# Gripper_Control_Board.net
KiCad netlist of a schematic drawn in EAGLE
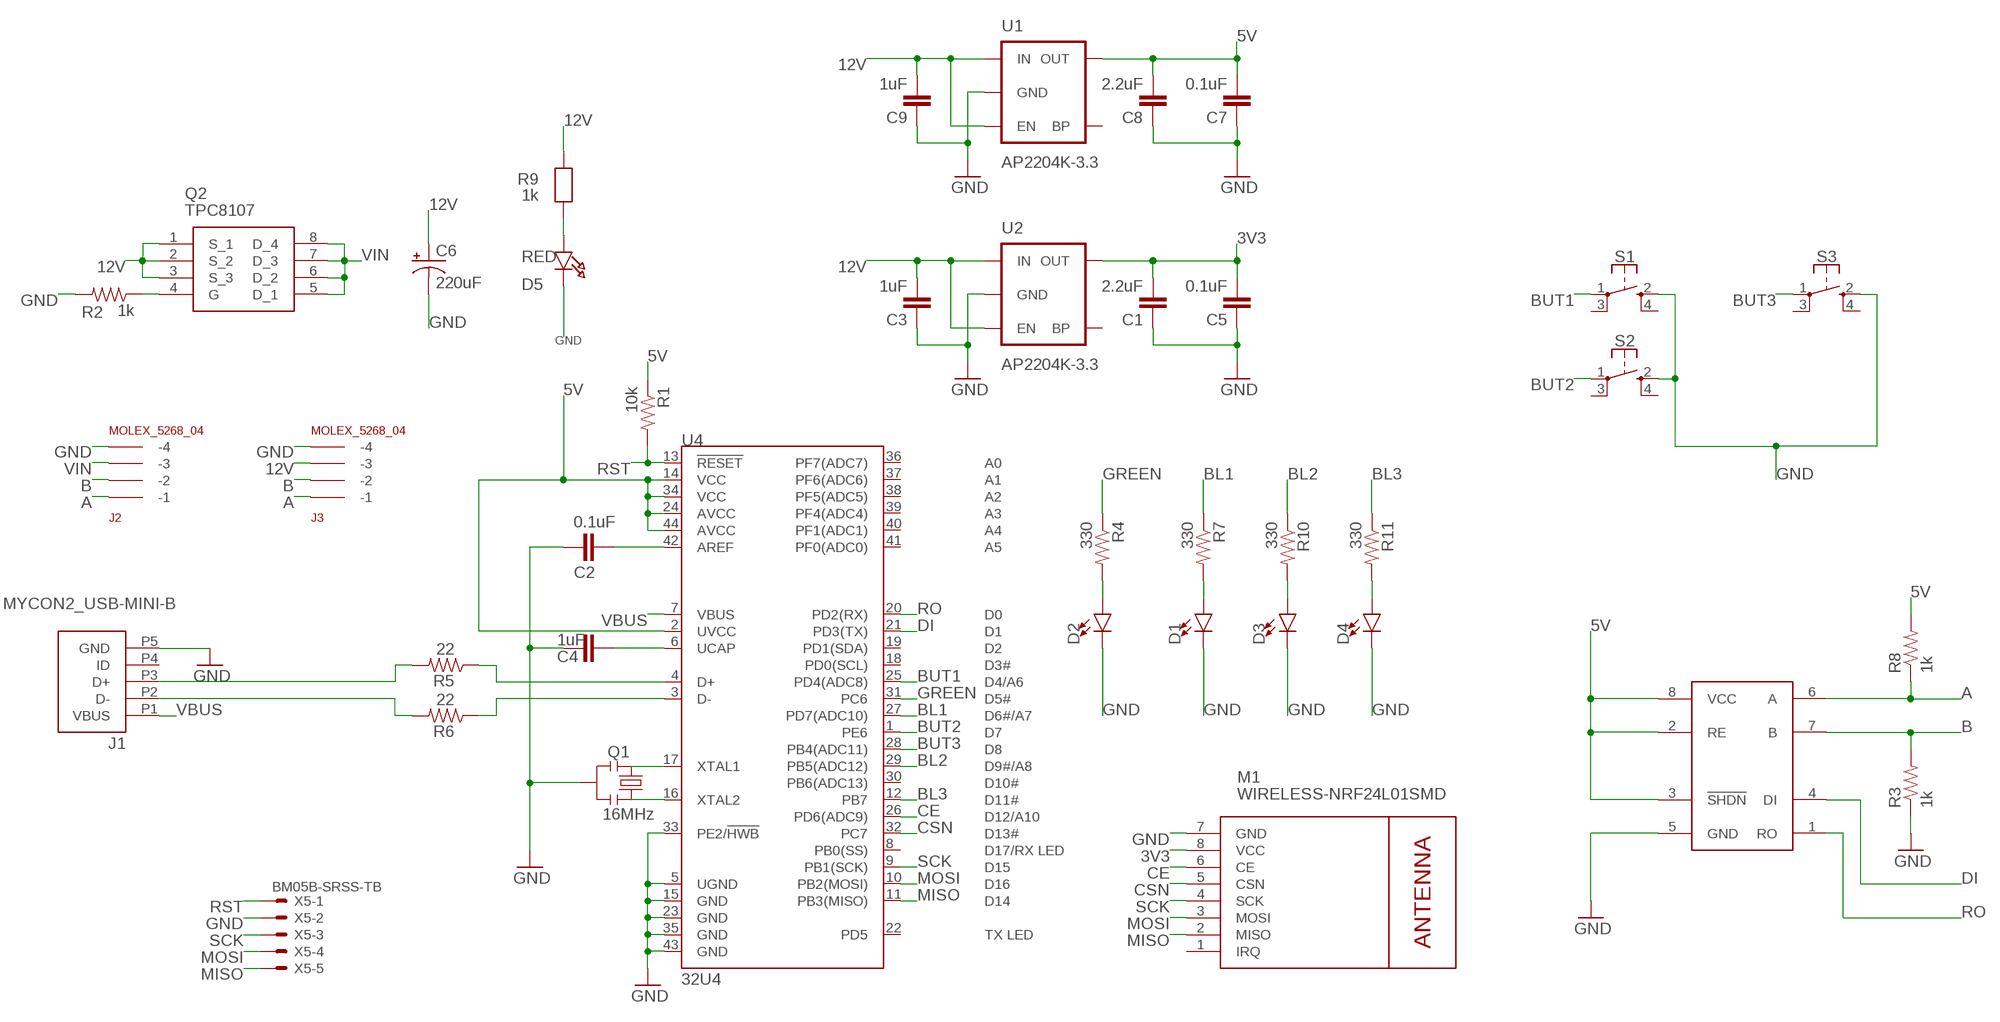
[diagram p0: schematic, sheet 1]

(export (version "E")
  (design (tool "Eeschema 10.0.6"))
  (components
    (comp (ref "C1")
      (value "2.2uF")
      (footprint "eagle-import:0603-CAP")
      (libsource (lib "eagle-import") (part "CAP0603-CAP"))
    )
    (comp (ref "C2")
      (value "0.1uF")
      (footprint "eagle-import:0603-CAP")
      (libsource (lib "eagle-import") (part "CAP0603-CAP"))
    )
    (comp (ref "C3")
      (value "1uF")
      (footprint "eagle-import:0603-CAP")
      (libsource (lib "eagle-import") (part "CAP0603-CAP"))
    )
    (comp (ref "C4")
      (value "1uF")
      (footprint "eagle-import:0603-CAP")
      (libsource (lib "eagle-import") (part "CAP0603-CAP"))
    )
    (comp (ref "C5")
      (value "0.1uF")
      (footprint "eagle-import:0603-CAP")
      (libsource (lib "eagle-import") (part "CAP0603-CAP"))
    )
    (comp (ref "C6")
      (value "220uF")
      (footprint "eagle-import:PANASONIC_D")
      (libsource (lib "eagle-import") (part "100UF-POLAR-25V-20%(ELEC)"))
    )
    (comp (ref "C7")
      (value "0.1uF")
      (footprint "eagle-import:0603-CAP")
      (libsource (lib "eagle-import") (part "CAP0603-CAP"))
    )
    (comp (ref "C8")
      (value "2.2uF")
      (footprint "eagle-import:0603-CAP")
      (libsource (lib "eagle-import") (part "CAP0603-CAP"))
    )
    (comp (ref "C9")
      (value "1uF")
      (footprint "eagle-import:0603-CAP")
      (libsource (lib "eagle-import") (part "CAP0603-CAP"))
    )
    (comp (ref "D1")
      (value "LED0603")
      (footprint "eagle-import:LED-0603")
      (libsource (lib "eagle-import") (part "LED0603"))
    )
    (comp (ref "D2")
      (value "LED0603")
      (footprint "eagle-import:LED-0603")
      (libsource (lib "eagle-import") (part "LED0603"))
    )
    (comp (ref "D3")
      (value "LED0603")
      (footprint "eagle-import:LED-0603")
      (libsource (lib "eagle-import") (part "LED0603"))
    )
    (comp (ref "D4")
      (value "LED0603")
      (footprint "eagle-import:LED-0603")
      (libsource (lib "eagle-import") (part "LED0603"))
    )
    (comp (ref "D5")
      (value "RED")
      (footprint "eagle-import:CHIPLED_0603")
      (libsource (lib "eagle-import") (part "microbuilder_LED0603"))
    )
    (comp (ref "J1")
      (value "MYCON2_USB-MINI-B")
      (footprint "eagle-import:CON2_USB_MICRO_B_AT")
      (libsource (lib "eagle-import") (part "MYCON2_USB-MINI-B"))
    )
    (comp (ref "J2")
      (value "MOLEX_5268_04")
      (footprint "eagle-import:5267-4")
      (libsource (lib "eagle-import") (part "MOLEX_5268_04"))
    )
    (comp (ref "J3")
      (value "MOLEX_5268_04")
      (footprint "eagle-import:5267-4")
      (libsource (lib "eagle-import") (part "MOLEX_5268_04"))
    )
    (comp (ref "M1")
      (value "WIRELESS-NRF24L01SMD")
      (footprint "eagle-import:WIRELESS-NRF24L01-SMD")
      (libsource (lib "eagle-import") (part "WIRELESS-NRF24L01SMD"))
    )
    (comp (ref "Q1")
      (value "16MHz")
      (footprint "eagle-import:RESONATOR-SMD")
      (libsource (lib "eagle-import") (part "RESONATORSMD"))
    )
    (comp (ref "Q2")
      (value "TPC8107")
      (footprint "eagle-import:SOIC127P600X175-8N")
      (fields
        (field (name "MANUFACTURER_PART_NUMBER") "DMG4413LSS-13")
        (field (name "MOUSER_PART_NUMBER") "621-DMG4413LSS-13")
        (field (name "RS_PART_NUMBER") "7514102P")
      )
      (libsource (lib "eagle-import") (part "TPC8107"))
    )
    (comp (ref "R1")
      (value "10k")
      (footprint "eagle-import:0603-RES")
      (libsource (lib "eagle-import") (part "RESISTOR0603"))
    )
    (comp (ref "R2")
      (value "1k")
      (footprint "eagle-import:0603")
      (libsource (lib "eagle-import") (part "1KOHM-0603-1/10W-1%"))
    )
    (comp (ref "R3")
      (value "1k")
      (footprint "eagle-import:0603-RES")
      (libsource (lib "eagle-import") (part "RESISTOR0603-RES"))
    )
    (comp (ref "R4")
      (value "330")
      (footprint "eagle-import:0603-RES")
      (libsource (lib "eagle-import") (part "RESISTOR0603"))
    )
    (comp (ref "R5")
      (value "22")
      (footprint "eagle-import:0603-RES")
      (fields (field (name "SPICEPREFIX") "R"))
      (libsource (lib "eagle-import") (part "RESISTOR0603"))
    )
    (comp (ref "R6")
      (value "22")
      (footprint "eagle-import:0603-RES")
      (libsource (lib "eagle-import") (part "RESISTOR0603"))
    )
    (comp (ref "R7")
      (value "330")
      (footprint "eagle-import:0603-RES")
      (fields (field (name "SPICEPREFIX") "R"))
      (libsource (lib "eagle-import") (part "RESISTOR0603"))
    )
    (comp (ref "R8")
      (value "1k")
      (footprint "eagle-import:0603-RES")
      (libsource (lib "eagle-import") (part "RESISTOR0603-RES"))
    )
    (comp (ref "R9")
      (value "1k")
      (footprint "eagle-import:0603-MINI")
      (libsource (lib "eagle-import") (part "RESISTOR0603MINI"))
    )
    (comp (ref "R10")
      (value "330")
      (footprint "eagle-import:0603-RES")
      (libsource (lib "eagle-import") (part "RESISTOR0603"))
    )
    (comp (ref "R11")
      (value "330")
      (footprint "eagle-import:0603-RES")
      (libsource (lib "eagle-import") (part "RESISTOR0603"))
    )
    (comp (ref "S1")
      (value "SKSGAAE010")
      (footprint "eagle-import:SKSG")
      (fields (field (name "MOUSER_PART_NUMBER") "688-SKSGAAE010"))
      (libsource (lib "eagle-import") (part "SKSGAAE010"))
    )
    (comp (ref "S2")
      (value "SKSGAAE010")
      (footprint "eagle-import:SKSG")
      (fields (field (name "MOUSER_PART_NUMBER") "688-SKSGAAE010"))
      (libsource (lib "eagle-import") (part "SKSGAAE010"))
    )
    (comp (ref "S3")
      (value "SKSGAAE010")
      (footprint "eagle-import:SKSG")
      (fields (field (name "MOUSER_PART_NUMBER") "688-SKSGAAE010"))
      (libsource (lib "eagle-import") (part "SKSGAAE010"))
    )
    (comp (ref "U1")
      (value "AP2204K-3.3")
      (footprint "eagle-import:SOT23-5")
      (libsource (lib "eagle-import") (part "V_REG_LDOSMD"))
    )
    (comp (ref "U2")
      (value "AP2204K-3.3")
      (footprint "eagle-import:SOT23-5")
      (libsource (lib "eagle-import") (part "V_REG_LDOSMD"))
    )
    (comp (ref "U3")
      (value "MAX13487")
      (footprint "eagle-import:MAX13487")
      (libsource (lib "eagle-import") (part "MAX13487SOIC"))
    )
    (comp (ref "U4")
      (value "32U4")
      (footprint "eagle-import:QFN-44-NOPAD")
      (libsource (lib "eagle-import") (part "ATMEGA32U4QFN2"))
    )
    (comp (ref "X5")
      (value "BM05B-SRSS-TB")
      (footprint "eagle-import:BM05B-SRSS-TB")
      (libsource (lib "eagle-import") (part "?M05B-SRSS-TBB"))
    )
  )
  (nets
    (net (code "1") (name "/3V3") (class "Default")
      (node (ref "C1") (pin "2") (pinfunction "2_2") (pintype "passive"))
      (node (ref "C5") (pin "2") (pinfunction "2_2") (pintype "passive"))
      (node (ref "M1") (pin "8") (pinfunction "VCC_8") (pintype "power_in"))
      (node (ref "U2") (pin "5") (pinfunction "OUT_5") (pintype "passive"))
    )
    (net (code "2") (name "/5V") (class "Default")
      (node (ref "C7") (pin "2") (pinfunction "2_2") (pintype "passive"))
      (node (ref "C8") (pin "2") (pinfunction "2_2") (pintype "passive"))
      (node (ref "R1") (pin "1") (pinfunction "1_1") (pintype "passive"))
      (node (ref "R8") (pin "2") (pinfunction "2_2") (pintype "passive"))
      (node (ref "U1") (pin "5") (pinfunction "OUT_5") (pintype "passive"))
      (node (ref "U3") (pin "2") (pinfunction "RE_2") (pintype "bidirectional"))
      (node (ref "U3") (pin "3") (pinfunction "~{SHDN}_3") (pintype "bidirectional"))
      (node (ref "U3") (pin "8") (pinfunction "VCC_8") (pintype "power_in"))
      (node (ref "U4") (pin "14") (pinfunction "VCC_14") (pintype "bidirectional"))
      (node (ref "U4") (pin "2") (pinfunction "UVCC_2") (pintype "bidirectional"))
      (node (ref "U4") (pin "24") (pinfunction "AVCC_24") (pintype "bidirectional"))
      (node (ref "U4") (pin "34") (pinfunction "VCC_34") (pintype "bidirectional"))
      (node (ref "U4") (pin "44") (pinfunction "AVCC_44") (pintype "bidirectional"))
    )
    (net (code "3") (name "/12V") (class "Default")
      (node (ref "C3") (pin "2") (pinfunction "2_2") (pintype "passive"))
      (node (ref "C6") (pin "+") (pinfunction "+_+") (pintype "passive"))
      (node (ref "C9") (pin "2") (pinfunction "2_2") (pintype "passive"))
      (node (ref "J3") (pin "P$3") (pinfunction "-3_P$3") (pintype "bidirectional"))
      (node (ref "Q2") (pin "1") (pinfunction "S_1_1") (pintype "bidirectional"))
      (node (ref "Q2") (pin "2") (pinfunction "S_2_2") (pintype "bidirectional"))
      (node (ref "Q2") (pin "3") (pinfunction "S_3_3") (pintype "bidirectional"))
      (node (ref "R9") (pin "2") (pinfunction "2_2") (pintype "passive"))
      (node (ref "U1") (pin "1") (pinfunction "IN_1") (pintype "input"))
      (node (ref "U1") (pin "3") (pinfunction "EN_3") (pintype "input"))
      (node (ref "U2") (pin "1") (pinfunction "IN_1") (pintype "input"))
      (node (ref "U2") (pin "3") (pinfunction "EN_3") (pintype "input"))
    )
    (net (code "4") (name "/A") (class "Default")
      (node (ref "J2") (pin "P$1") (pinfunction "-1_P$1") (pintype "bidirectional"))
      (node (ref "J3") (pin "P$1") (pinfunction "-1_P$1") (pintype "bidirectional"))
      (node (ref "R8") (pin "1") (pinfunction "1_1") (pintype "passive"))
      (node (ref "U3") (pin "6") (pinfunction "A_6") (pintype "bidirectional"))
    )
    (net (code "5") (name "/B") (class "Default")
      (node (ref "J2") (pin "P$2") (pinfunction "-2_P$2") (pintype "bidirectional"))
      (node (ref "J3") (pin "P$2") (pinfunction "-2_P$2") (pintype "bidirectional"))
      (node (ref "R3") (pin "2") (pinfunction "2_2") (pintype "passive"))
      (node (ref "U3") (pin "7") (pinfunction "B_7") (pintype "bidirectional"))
    )
    (net (code "6") (name "/BL1") (class "Default")
      (node (ref "R7") (pin "1") (pinfunction "1_1") (pintype "passive"))
      (node (ref "U4") (pin "27") (pinfunction "PD7(ADC10)_27") (pintype "bidirectional"))
    )
    (net (code "7") (name "/BL2") (class "Default")
      (node (ref "R10") (pin "1") (pinfunction "1_1") (pintype "passive"))
      (node (ref "U4") (pin "29") (pinfunction "PB5(ADC12)_29") (pintype "bidirectional"))
    )
    (net (code "8") (name "/BL3") (class "Default")
      (node (ref "R11") (pin "1") (pinfunction "1_1") (pintype "passive"))
      (node (ref "U4") (pin "12") (pinfunction "PB7_12") (pintype "bidirectional"))
    )
    (net (code "9") (name "/BUT1") (class "Default")
      (node (ref "S1") (pin "1") (pinfunction "1_1") (pintype "passive"))
      (node (ref "U4") (pin "25") (pinfunction "PD4(ADC8)_25") (pintype "bidirectional"))
    )
    (net (code "10") (name "/BUT2") (class "Default")
      (node (ref "S2") (pin "1") (pinfunction "1_1") (pintype "passive"))
      (node (ref "U4") (pin "1") (pinfunction "PE6_1") (pintype "bidirectional"))
    )
    (net (code "11") (name "/BUT3") (class "Default")
      (node (ref "S3") (pin "1") (pinfunction "1_1") (pintype "passive"))
      (node (ref "U4") (pin "28") (pinfunction "PB4(ADC11)_28") (pintype "bidirectional"))
    )
    (net (code "12") (name "/CE") (class "Default")
      (node (ref "M1") (pin "6") (pinfunction "CE_6") (pintype "bidirectional"))
      (node (ref "U4") (pin "26") (pinfunction "PD6(ADC9)_26") (pintype "bidirectional"))
    )
    (net (code "13") (name "/CSN") (class "Default")
      (node (ref "M1") (pin "5") (pinfunction "CSN_5") (pintype "bidirectional"))
      (node (ref "U4") (pin "32") (pinfunction "PC7_32") (pintype "bidirectional"))
    )
    (net (code "14") (name "/DI") (class "Default")
      (node (ref "U3") (pin "4") (pinfunction "DI_4") (pintype "input"))
      (node (ref "U4") (pin "21") (pinfunction "PD3(TX)_21") (pintype "bidirectional"))
    )
    (net (code "15") (name "/GREEN") (class "Default")
      (node (ref "R4") (pin "1") (pinfunction "1_1") (pintype "passive"))
      (node (ref "U4") (pin "31") (pinfunction "PC6_31") (pintype "bidirectional"))
    )
    (net (code "16") (name "/MISO") (class "Default")
      (node (ref "M1") (pin "2") (pinfunction "MISO_2") (pintype "bidirectional"))
      (node (ref "U4") (pin "11") (pinfunction "PB3(MISO)_11") (pintype "bidirectional"))
      (node (ref "X5") (pin "5") (pinfunction "S_5") (pintype "passive"))
    )
    (net (code "17") (name "/MOSI") (class "Default")
      (node (ref "M1") (pin "3") (pinfunction "MOSI_3") (pintype "bidirectional"))
      (node (ref "U4") (pin "10") (pinfunction "PB2(MOSI)_10") (pintype "bidirectional"))
      (node (ref "X5") (pin "4") (pinfunction "S_4") (pintype "passive"))
    )
    (net (code "18") (name "/RO") (class "Default")
      (node (ref "U3") (pin "1") (pinfunction "RO_1") (pintype "output"))
      (node (ref "U4") (pin "20") (pinfunction "PD2(RX)_20") (pintype "bidirectional"))
    )
    (net (code "19") (name "/RST") (class "Default")
      (node (ref "R1") (pin "2") (pinfunction "2_2") (pintype "passive"))
      (node (ref "U4") (pin "13") (pinfunction "~{RESET}_13") (pintype "bidirectional"))
      (node (ref "X5") (pin "1") (pinfunction "S_1") (pintype "passive"))
    )
    (net (code "20") (name "/SCK") (class "Default")
      (node (ref "M1") (pin "4") (pinfunction "SCK_4") (pintype "bidirectional"))
      (node (ref "U4") (pin "9") (pinfunction "PB1(SCK)_9") (pintype "bidirectional"))
      (node (ref "X5") (pin "3") (pinfunction "S_3") (pintype "passive"))
    )
    (net (code "21") (name "/VBUS") (class "Default")
      (node (ref "J1") (pin "P1") (pinfunction "VBUS_P1") (pintype "power_in"))
      (node (ref "U4") (pin "7") (pinfunction "VBUS_7") (pintype "bidirectional"))
    )
    (net (code "22") (name "/VIN") (class "Default")
      (node (ref "J2") (pin "P$3") (pinfunction "-3_P$3") (pintype "bidirectional"))
      (node (ref "Q2") (pin "5") (pinfunction "D_1_5") (pintype "bidirectional"))
      (node (ref "Q2") (pin "6") (pinfunction "D_2_6") (pintype "bidirectional"))
      (node (ref "Q2") (pin "7") (pinfunction "D_3_7") (pintype "bidirectional"))
      (node (ref "Q2") (pin "8") (pinfunction "D_4_8") (pintype "bidirectional"))
    )
    (net (code "23") (name "GND") (class "Default")
      (node (ref "C1") (pin "1") (pinfunction "1_1") (pintype "passive"))
      (node (ref "C2") (pin "1") (pinfunction "1_1") (pintype "passive"))
      (node (ref "C3") (pin "1") (pinfunction "1_1") (pintype "passive"))
      (node (ref "C4") (pin "1") (pinfunction "1_1") (pintype "passive"))
      (node (ref "C5") (pin "1") (pinfunction "1_1") (pintype "passive"))
      (node (ref "C6") (pin "-") (pinfunction "-_-") (pintype "passive"))
      (node (ref "C7") (pin "1") (pinfunction "1_1") (pintype "passive"))
      (node (ref "C8") (pin "1") (pinfunction "1_1") (pintype "passive"))
      (node (ref "C9") (pin "1") (pinfunction "1_1") (pintype "passive"))
      (node (ref "D1") (pin "C") (pinfunction "C_C") (pintype "passive"))
      (node (ref "D2") (pin "C") (pinfunction "C_C") (pintype "passive"))
      (node (ref "D3") (pin "C") (pinfunction "C_C") (pintype "passive"))
      (node (ref "D4") (pin "C") (pinfunction "C_C") (pintype "passive"))
      (node (ref "D5") (pin "C") (pinfunction "C_C") (pintype "passive"))
      (node (ref "J1") (pin "P5") (pinfunction "GND_P5") (pintype "passive"))
      (node (ref "J2") (pin "P$4") (pinfunction "-4_P$4") (pintype "bidirectional"))
      (node (ref "J3") (pin "P$4") (pinfunction "-4_P$4") (pintype "bidirectional"))
      (node (ref "M1") (pin "7") (pinfunction "GND_7") (pintype "power_in"))
      (node (ref "Q1") (pin "2") (pinfunction "2_2") (pintype "passive"))
      (node (ref "R2") (pin "2") (pinfunction "2_2") (pintype "passive"))
      (node (ref "R3") (pin "1") (pinfunction "1_1") (pintype "passive"))
      (node (ref "S1") (pin "2") (pinfunction "3_2") (pintype "passive"))
      (node (ref "S2") (pin "2") (pinfunction "3_2") (pintype "passive"))
      (node (ref "S3") (pin "2") (pinfunction "3_2") (pintype "passive"))
      (node (ref "U1") (pin "2") (pinfunction "GND_2") (pintype "input"))
      (node (ref "U2") (pin "2") (pinfunction "GND_2") (pintype "input"))
      (node (ref "U3") (pin "5") (pinfunction "GND_5") (pintype "power_in"))
      (node (ref "U4") (pin "15") (pinfunction "GND_15") (pintype "bidirectional"))
      (node (ref "U4") (pin "23") (pinfunction "GND_23") (pintype "bidirectional"))
      (node (ref "U4") (pin "33") (pinfunction "PE2/~{HWB}_33") (pintype "bidirectional"))
      (node (ref "U4") (pin "35") (pinfunction "GND_35") (pintype "bidirectional"))
      (node (ref "U4") (pin "43") (pinfunction "GND_43") (pintype "bidirectional"))
      (node (ref "U4") (pin "5") (pinfunction "UGND_5") (pintype "bidirectional"))
      (node (ref "X5") (pin "2") (pinfunction "S_2") (pintype "passive"))
    )
    (net (code "24") (name "Net-(D1-PadA)") (class "Default")
      (node (ref "D1") (pin "A") (pinfunction "A_A") (pintype "passive"))
      (node (ref "R7") (pin "2") (pinfunction "2_2") (pintype "passive"))
    )
    (net (code "25") (name "Net-(D2-PadA)") (class "Default")
      (node (ref "D2") (pin "A") (pinfunction "A_A") (pintype "passive"))
      (node (ref "R4") (pin "2") (pinfunction "2_2") (pintype "passive"))
    )
    (net (code "26") (name "Net-(D3-PadA)") (class "Default")
      (node (ref "D3") (pin "A") (pinfunction "A_A") (pintype "passive"))
      (node (ref "R10") (pin "2") (pinfunction "2_2") (pintype "passive"))
    )
    (net (code "27") (name "Net-(D4-PadA)") (class "Default")
      (node (ref "D4") (pin "A") (pinfunction "A_A") (pintype "passive"))
      (node (ref "R11") (pin "2") (pinfunction "2_2") (pintype "passive"))
    )
    (net (code "28") (name "Net-(D5-PadA)") (class "Default")
      (node (ref "D5") (pin "A") (pinfunction "A_A") (pintype "passive"))
      (node (ref "R9") (pin "1") (pinfunction "1_1") (pintype "passive"))
    )
    (net (code "29") (name "Net-(J1-D+)") (class "Default")
      (node (ref "J1") (pin "P3") (pinfunction "D+_P3") (pintype "bidirectional"))
      (node (ref "R5") (pin "2") (pinfunction "2_2") (pintype "passive"))
    )
    (net (code "30") (name "Net-(J1-D-)") (class "Default")
      (node (ref "J1") (pin "P2") (pinfunction "D-_P2") (pintype "bidirectional"))
      (node (ref "R6") (pin "2") (pinfunction "2_2") (pintype "passive"))
    )
    (net (code "31") (name "Net-(Q2-G)") (class "Default")
      (node (ref "Q2") (pin "4") (pinfunction "G_4") (pintype "bidirectional"))
      (node (ref "R2") (pin "1") (pinfunction "1_1") (pintype "passive"))
    )
    (net (code "32") (name "Net-(U4-AREF)") (class "Default")
      (node (ref "C2") (pin "2") (pinfunction "2_2") (pintype "passive"))
      (node (ref "U4") (pin "42") (pinfunction "AREF_42") (pintype "bidirectional"))
    )
    (net (code "33") (name "Net-(U4-D+)") (class "Default")
      (node (ref "R5") (pin "1") (pinfunction "1_1") (pintype "passive"))
      (node (ref "U4") (pin "4") (pinfunction "D+_4") (pintype "bidirectional"))
    )
    (net (code "34") (name "Net-(U4-D-)") (class "Default")
      (node (ref "R6") (pin "1") (pinfunction "1_1") (pintype "passive"))
      (node (ref "U4") (pin "3") (pinfunction "D-_3") (pintype "bidirectional"))
    )
    (net (code "35") (name "Net-(U4-UCAP)") (class "Default")
      (node (ref "C4") (pin "2") (pinfunction "2_2") (pintype "passive"))
      (node (ref "U4") (pin "6") (pinfunction "UCAP_6") (pintype "bidirectional"))
    )
    (net (code "36") (name "Net-(U4-XTAL1)") (class "Default")
      (node (ref "Q1") (pin "1") (pinfunction "1_1") (pintype "passive"))
      (node (ref "U4") (pin "17") (pinfunction "XTAL1_17") (pintype "bidirectional"))
    )
    (net (code "37") (name "Net-(U4-XTAL2)") (class "Default")
      (node (ref "Q1") (pin "3") (pinfunction "3_3") (pintype "passive"))
      (node (ref "U4") (pin "16") (pinfunction "XTAL2_16") (pintype "bidirectional"))
    )
    (net (code "38") (name "unconnected-(J1-ID-PadP4)") (class "Default")
      (node (ref "J1") (pin "P4") (pinfunction "ID_P4") (pintype "bidirectional"))
    )
    (net (code "39") (name "unconnected-(M1-IRQ-Pad1)") (class "Default")
      (node (ref "M1") (pin "1") (pinfunction "IRQ_1") (pintype "bidirectional"))
    )
    (net (code "40") (name "unconnected-(S1-2-Pad3)") (class "Default")
      (node (ref "S1") (pin "3") (pinfunction "2_3") (pintype "passive"))
    )
    (net (code "41") (name "unconnected-(S1-Pad4)") (class "Default")
      (node (ref "S1") (pin "4") (pinfunction "4_4") (pintype "passive"))
    )
    (net (code "42") (name "unconnected-(S2-2-Pad3)") (class "Default")
      (node (ref "S2") (pin "3") (pinfunction "2_3") (pintype "passive"))
    )
    (net (code "43") (name "unconnected-(S2-Pad4)") (class "Default")
      (node (ref "S2") (pin "4") (pinfunction "4_4") (pintype "passive"))
    )
    (net (code "44") (name "unconnected-(S3-2-Pad3)") (class "Default")
      (node (ref "S3") (pin "3") (pinfunction "2_3") (pintype "passive"))
    )
    (net (code "45") (name "unconnected-(S3-Pad4)") (class "Default")
      (node (ref "S3") (pin "4") (pinfunction "4_4") (pintype "passive"))
    )
    (net (code "46") (name "unconnected-(U1-BP-Pad4)") (class "Default")
      (node (ref "U1") (pin "4") (pinfunction "BP_4") (pintype "input"))
    )
    (net (code "47") (name "unconnected-(U2-BP-Pad4)") (class "Default")
      (node (ref "U2") (pin "4") (pinfunction "BP_4") (pintype "input"))
    )
    (net (code "48") (name "unconnected-(U4-PB0(SS)-Pad8)") (class "Default")
      (node (ref "U4") (pin "8") (pinfunction "PB0(SS)_8") (pintype "bidirectional"))
    )
    (net (code "49") (name "unconnected-(U4-PB6(ADC13)-Pad30)") (class "Default")
      (node (ref "U4") (pin "30") (pinfunction "PB6(ADC13)_30") (pintype "bidirectional"))
    )
    (net (code "50") (name "unconnected-(U4-PD0(SCL)-Pad18)") (class "Default")
      (node (ref "U4") (pin "18") (pinfunction "PD0(SCL)_18") (pintype "bidirectional"))
    )
    (net (code "51") (name "unconnected-(U4-PD1(SDA)-Pad19)") (class "Default")
      (node (ref "U4") (pin "19") (pinfunction "PD1(SDA)_19") (pintype "bidirectional"))
    )
    (net (code "52") (name "unconnected-(U4-PD5-Pad22)") (class "Default")
      (node (ref "U4") (pin "22") (pinfunction "PD5_22") (pintype "bidirectional"))
    )
    (net (code "53") (name "unconnected-(U4-PF0(ADC0)-Pad41)") (class "Default")
      (node (ref "U4") (pin "41") (pinfunction "PF0(ADC0)_41") (pintype "bidirectional"))
    )
    (net (code "54") (name "unconnected-(U4-PF1(ADC1)-Pad40)") (class "Default")
      (node (ref "U4") (pin "40") (pinfunction "PF1(ADC1)_40") (pintype "bidirectional"))
    )
    (net (code "55") (name "unconnected-(U4-PF4(ADC4)-Pad39)") (class "Default")
      (node (ref "U4") (pin "39") (pinfunction "PF4(ADC4)_39") (pintype "bidirectional"))
    )
    (net (code "56") (name "unconnected-(U4-PF5(ADC5)-Pad38)") (class "Default")
      (node (ref "U4") (pin "38") (pinfunction "PF5(ADC5)_38") (pintype "bidirectional"))
    )
    (net (code "57") (name "unconnected-(U4-PF6(ADC6)-Pad37)") (class "Default")
      (node (ref "U4") (pin "37") (pinfunction "PF6(ADC6)_37") (pintype "bidirectional"))
    )
    (net (code "58") (name "unconnected-(U4-PF7(ADC7)-Pad36)") (class "Default")
      (node (ref "U4") (pin "36") (pinfunction "PF7(ADC7)_36") (pintype "bidirectional"))
    )
  )
)
